# 7segement4digits1badidea-many-digits-mk-.net
KiCad netlist of a schematic drawn in EAGLE
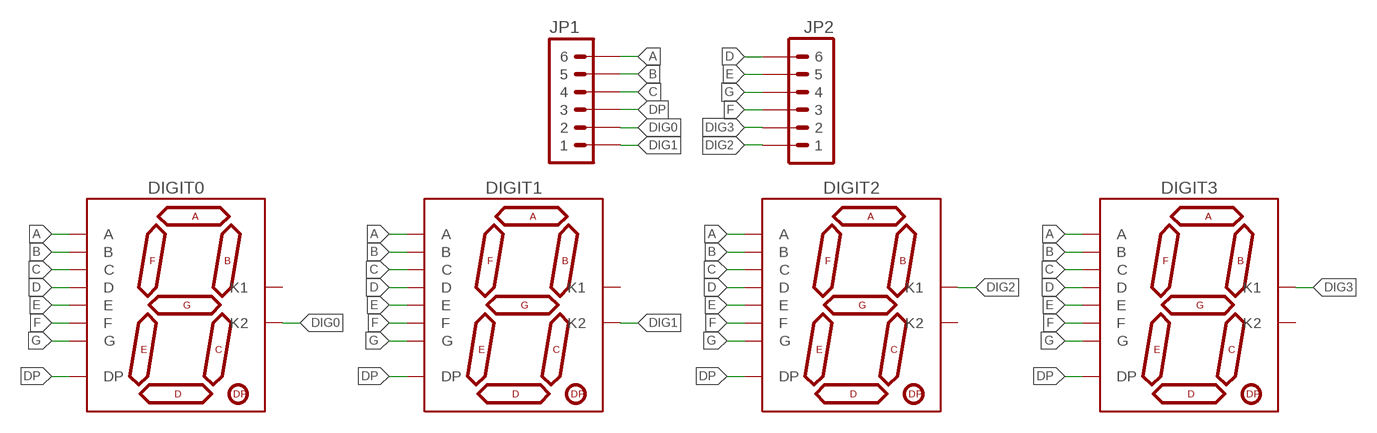
[diagram p0: schematic, sheet 1]

(export (version "E")
  (design (tool "Eeschema 10.0.6"))
  (components
    (comp (ref "DIGIT0")
      (value "7SEG_1DIGPTH-10MM")
      (footprint "eagle-import:7SEG_1DIG_10MM")
      (libsource (lib "eagle-import") (part "7SEG_1DIGPTH-10MM"))
    )
    (comp (ref "DIGIT1")
      (value "7SEG_1DIGPTH-10MM")
      (footprint "eagle-import:7SEG_1DIG_10MM")
      (libsource (lib "eagle-import") (part "7SEG_1DIGPTH-10MM"))
    )
    (comp (ref "DIGIT2")
      (value "7SEG_1DIGPTH-10MM")
      (footprint "eagle-import:7SEG_1DIG_10MM")
      (libsource (lib "eagle-import") (part "7SEG_1DIGPTH-10MM"))
    )
    (comp (ref "DIGIT3")
      (value "7SEG_1DIGPTH-10MM")
      (footprint "eagle-import:7SEG_1DIG_10MM")
      (libsource (lib "eagle-import") (part "7SEG_1DIGPTH-10MM"))
    )
    (comp (ref "JP1")
      (value "M06-NOBS-PTH")
      (footprint "eagle-import:1X06_NOLOCK_FUCKITALL")
      (libsource (lib "eagle-import") (part "M06-NOBS-PTH"))
    )
    (comp (ref "JP2")
      (value "M06-NOBS-PTH")
      (footprint "eagle-import:1X06_NOLOCK_FUCKITALL")
      (libsource (lib "eagle-import") (part "M06-NOBS-PTH"))
    )
  )
  (nets
    (net (code "1") (name "A") (class "Default")
      (node (ref "DIGIT0") (pin "10") (pinfunction "A_10") (pintype "bidirectional"))
      (node (ref "DIGIT1") (pin "10") (pinfunction "A_10") (pintype "bidirectional"))
      (node (ref "DIGIT2") (pin "10") (pinfunction "A_10") (pintype "bidirectional"))
      (node (ref "DIGIT3") (pin "10") (pinfunction "A_10") (pintype "bidirectional"))
      (node (ref "JP1") (pin "6") (pinfunction "6_6") (pintype "passive"))
    )
    (net (code "2") (name "B") (class "Default")
      (node (ref "DIGIT0") (pin "9") (pinfunction "B_9") (pintype "bidirectional"))
      (node (ref "DIGIT1") (pin "9") (pinfunction "B_9") (pintype "bidirectional"))
      (node (ref "DIGIT2") (pin "9") (pinfunction "B_9") (pintype "bidirectional"))
      (node (ref "DIGIT3") (pin "9") (pinfunction "B_9") (pintype "bidirectional"))
      (node (ref "JP1") (pin "5") (pinfunction "5_5") (pintype "passive"))
    )
    (net (code "3") (name "C") (class "Default")
      (node (ref "DIGIT0") (pin "8") (pinfunction "C_8") (pintype "bidirectional"))
      (node (ref "DIGIT1") (pin "8") (pinfunction "C_8") (pintype "bidirectional"))
      (node (ref "DIGIT2") (pin "8") (pinfunction "C_8") (pintype "bidirectional"))
      (node (ref "DIGIT3") (pin "8") (pinfunction "C_8") (pintype "bidirectional"))
      (node (ref "JP1") (pin "4") (pinfunction "4_4") (pintype "passive"))
    )
    (net (code "4") (name "D") (class "Default")
      (node (ref "DIGIT0") (pin "5") (pinfunction "D_5") (pintype "bidirectional"))
      (node (ref "DIGIT1") (pin "5") (pinfunction "D_5") (pintype "bidirectional"))
      (node (ref "DIGIT2") (pin "5") (pinfunction "D_5") (pintype "bidirectional"))
      (node (ref "DIGIT3") (pin "5") (pinfunction "D_5") (pintype "bidirectional"))
      (node (ref "JP2") (pin "6") (pinfunction "6_6") (pintype "passive"))
    )
    (net (code "5") (name "DIG0") (class "Default")
      (node (ref "DIGIT0") (pin "6") (pinfunction "K2_6") (pintype "bidirectional"))
      (node (ref "JP1") (pin "2") (pinfunction "2_2") (pintype "passive"))
    )
    (net (code "6") (name "DIG1") (class "Default")
      (node (ref "DIGIT1") (pin "6") (pinfunction "K2_6") (pintype "bidirectional"))
      (node (ref "JP1") (pin "1") (pinfunction "1_1") (pintype "passive"))
    )
    (net (code "7") (name "DIG2") (class "Default")
      (node (ref "DIGIT2") (pin "1") (pinfunction "K1_1") (pintype "bidirectional"))
      (node (ref "JP2") (pin "1") (pinfunction "1_1") (pintype "passive"))
    )
    (net (code "8") (name "DIG3") (class "Default")
      (node (ref "DIGIT3") (pin "1") (pinfunction "K1_1") (pintype "bidirectional"))
      (node (ref "JP2") (pin "2") (pinfunction "2_2") (pintype "passive"))
    )
    (net (code "9") (name "DP") (class "Default")
      (node (ref "DIGIT0") (pin "7") (pinfunction "DP_7") (pintype "bidirectional"))
      (node (ref "DIGIT1") (pin "7") (pinfunction "DP_7") (pintype "bidirectional"))
      (node (ref "DIGIT2") (pin "7") (pinfunction "DP_7") (pintype "bidirectional"))
      (node (ref "DIGIT3") (pin "7") (pinfunction "DP_7") (pintype "bidirectional"))
      (node (ref "JP1") (pin "3") (pinfunction "3_3") (pintype "passive"))
    )
    (net (code "10") (name "E") (class "Default")
      (node (ref "DIGIT0") (pin "4") (pinfunction "E_4") (pintype "bidirectional"))
      (node (ref "DIGIT1") (pin "4") (pinfunction "E_4") (pintype "bidirectional"))
      (node (ref "DIGIT2") (pin "4") (pinfunction "E_4") (pintype "bidirectional"))
      (node (ref "DIGIT3") (pin "4") (pinfunction "E_4") (pintype "bidirectional"))
      (node (ref "JP2") (pin "5") (pinfunction "5_5") (pintype "passive"))
    )
    (net (code "11") (name "F") (class "Default")
      (node (ref "DIGIT0") (pin "2") (pinfunction "F_2") (pintype "bidirectional"))
      (node (ref "DIGIT1") (pin "2") (pinfunction "F_2") (pintype "bidirectional"))
      (node (ref "DIGIT2") (pin "2") (pinfunction "F_2") (pintype "bidirectional"))
      (node (ref "DIGIT3") (pin "2") (pinfunction "F_2") (pintype "bidirectional"))
      (node (ref "JP2") (pin "3") (pinfunction "3_3") (pintype "passive"))
    )
    (net (code "12") (name "G") (class "Default")
      (node (ref "DIGIT0") (pin "3") (pinfunction "G_3") (pintype "bidirectional"))
      (node (ref "DIGIT1") (pin "3") (pinfunction "G_3") (pintype "bidirectional"))
      (node (ref "DIGIT2") (pin "3") (pinfunction "G_3") (pintype "bidirectional"))
      (node (ref "DIGIT3") (pin "3") (pinfunction "G_3") (pintype "bidirectional"))
      (node (ref "JP2") (pin "4") (pinfunction "4_4") (pintype "passive"))
    )
    (net (code "13") (name "unconnected-(DIGIT0-K1-Pad1)") (class "Default")
      (node (ref "DIGIT0") (pin "1") (pinfunction "K1_1") (pintype "bidirectional"))
    )
    (net (code "14") (name "unconnected-(DIGIT1-K1-Pad1)") (class "Default")
      (node (ref "DIGIT1") (pin "1") (pinfunction "K1_1") (pintype "bidirectional"))
    )
    (net (code "15") (name "unconnected-(DIGIT2-K2-Pad6)") (class "Default")
      (node (ref "DIGIT2") (pin "6") (pinfunction "K2_6") (pintype "bidirectional"))
    )
    (net (code "16") (name "unconnected-(DIGIT3-K2-Pad6)") (class "Default")
      (node (ref "DIGIT3") (pin "6") (pinfunction "K2_6") (pintype "bidirectional"))
    )
  )
)
